# blinkm_mk2b3.net
KiCad netlist of a schematic drawn in EAGLE
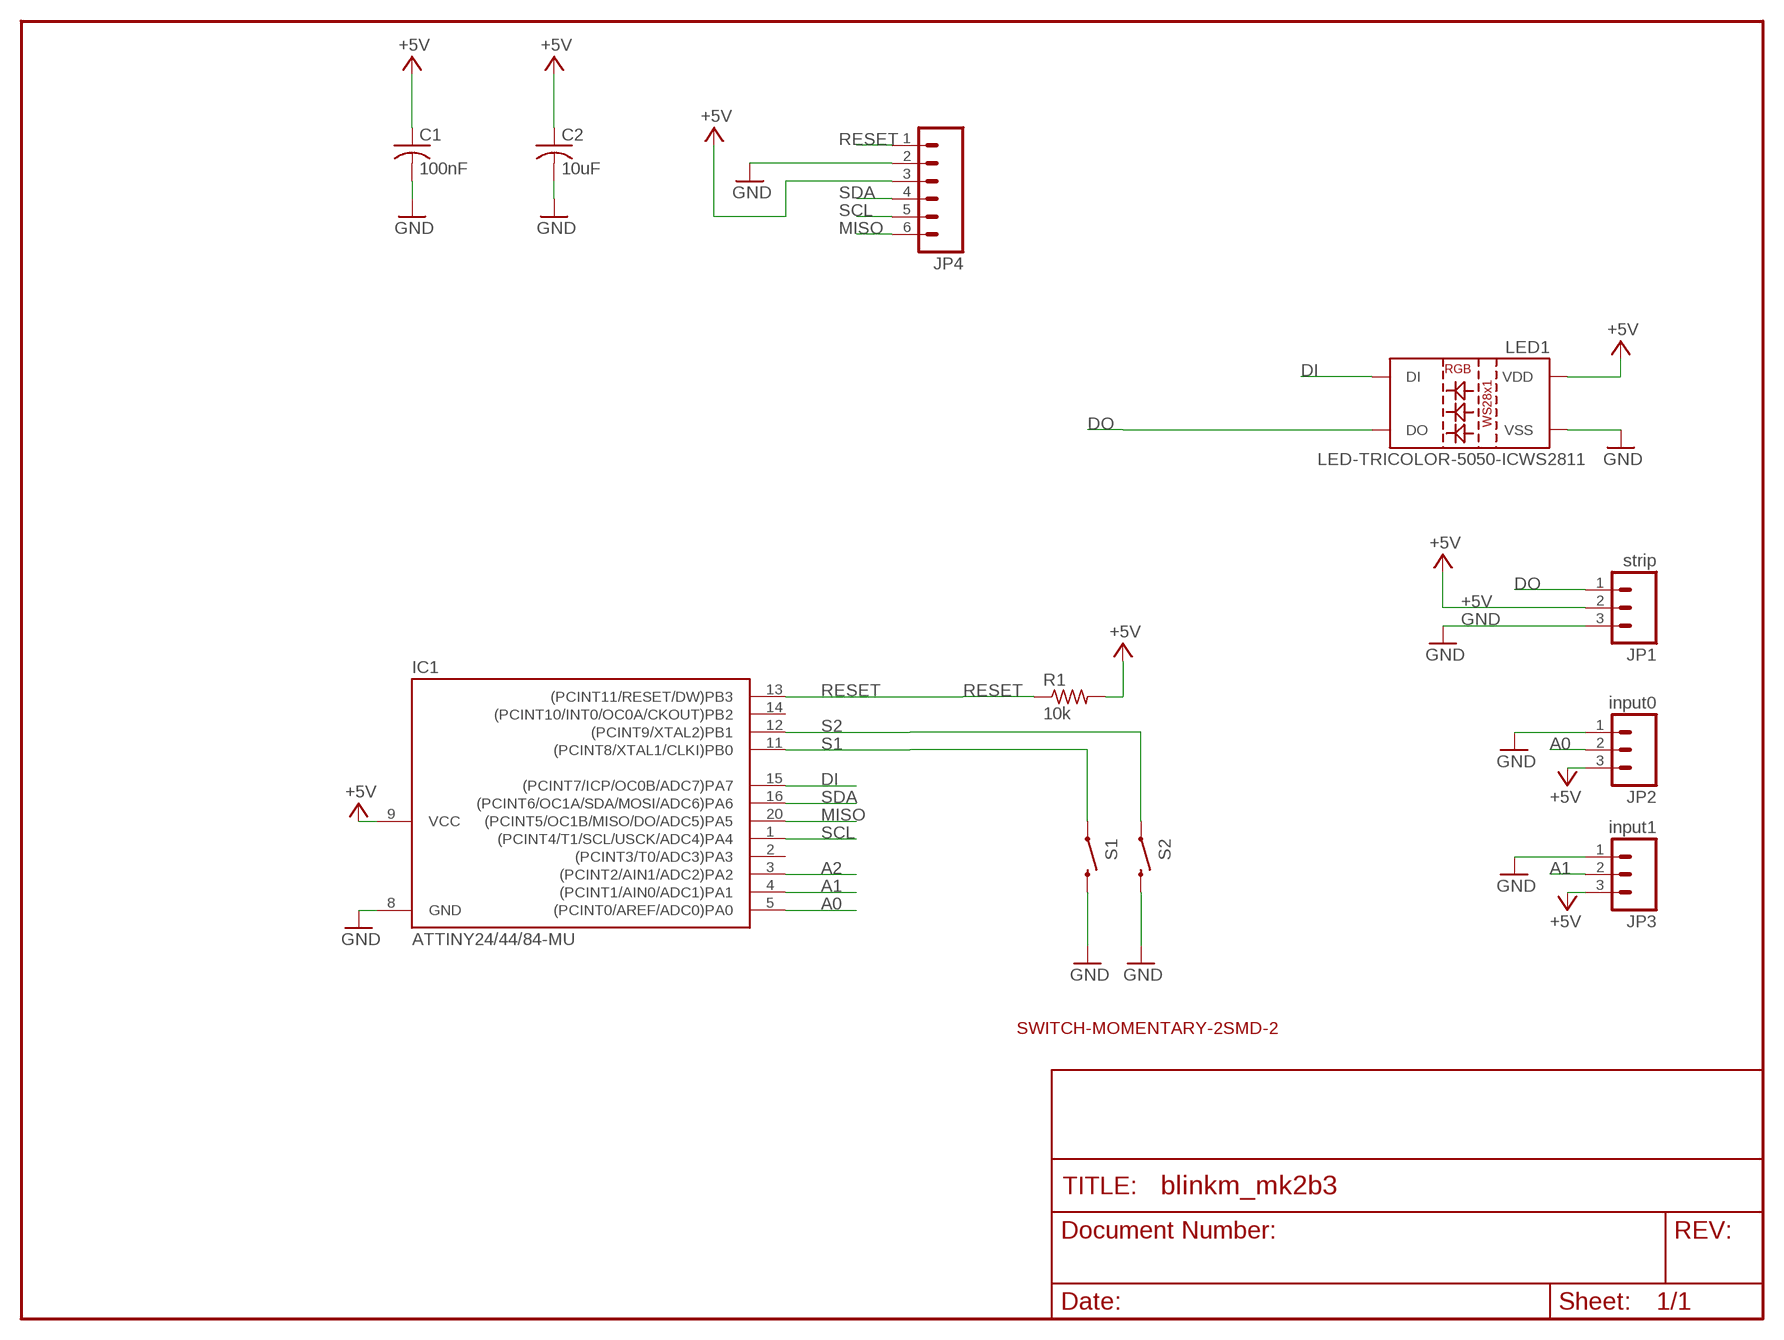
[diagram p0: schematic, sheet 1]

(export (version "E")
  (design (tool "Eeschema 10.0.6"))
  (components
    (comp (ref "C1")
      (value "100nF")
      (footprint "eagle-import:C0603")
      (libsource (lib "eagle-import") (part "C-USC0603"))
    )
    (comp (ref "C2")
      (value "10uF")
      (footprint "eagle-import:C0603")
      (libsource (lib "eagle-import") (part "C-USC0603"))
    )
    (comp (ref "IC1")
      (value "ATTINY24/44/84-MU")
      (footprint "eagle-import:QFN_MLF20")
      (libsource (lib "eagle-import") (part "ATTINY24/44/84-MU"))
    )
    (comp (ref "JP1")
      (value "strip")
      (footprint "eagle-import:1X03")
      (libsource (lib "eagle-import") (part "M03PTH"))
    )
    (comp (ref "JP2")
      (value "input0")
      (footprint "eagle-import:1X03")
      (libsource (lib "eagle-import") (part "M03PTH"))
    )
    (comp (ref "JP3")
      (value "input1")
      (footprint "eagle-import:1X03")
      (libsource (lib "eagle-import") (part "M03PTH"))
    )
    (comp (ref "JP4")
      (value "M06SIP")
      (footprint "eagle-import:1X06")
      (libsource (lib "eagle-import") (part "M06SIP"))
    )
    (comp (ref "LED1")
      (value "LED-TRICOLOR-5050-ICWS2811")
      (footprint "eagle-import:LED-TRICOLOR-5050-IC")
      (libsource (lib "eagle-import") (part "LED-TRICOLOR-5050-ICWS2811"))
    )
    (comp (ref "R1")
      (value "10k")
      (footprint "eagle-import:R0603")
      (libsource (lib "eagle-import") (part "R-US_R0603"))
    )
    (comp (ref "S1")
      (value "SWITCH-MOMENTARY-2SMD-2")
      (footprint "eagle-import:TACTILE_SWITCH_SMD-2")
      (libsource (lib "eagle-import") (part "SWITCH-MOMENTARY-2SMD-2"))
    )
    (comp (ref "S2")
      (value "SWITCH-MOMENTARY-2SMD-2")
      (footprint "eagle-import:TACTILE_SWITCH_SMD-2")
      (libsource (lib "eagle-import") (part "SWITCH-MOMENTARY-2SMD-2"))
    )
  )
  (nets
    (net (code "1") (name "+5V") (class "Default")
      (node (ref "C1") (pin "1") (pinfunction "1_1") (pintype "passive"))
      (node (ref "C2") (pin "1") (pinfunction "1_1") (pintype "passive"))
      (node (ref "IC1") (pin "9") (pinfunction "VCC_9") (pintype "power_in"))
      (node (ref "JP1") (pin "2") (pinfunction "2_2") (pintype "passive"))
      (node (ref "JP2") (pin "3") (pinfunction "3_3") (pintype "passive"))
      (node (ref "JP3") (pin "3") (pinfunction "3_3") (pintype "passive"))
      (node (ref "JP4") (pin "3") (pinfunction "3_3") (pintype "passive"))
      (node (ref "LED1") (pin "3") (pinfunction "VDD_3") (pintype "bidirectional"))
      (node (ref "LED1") (pin "5") (pinfunction "VDD_5") (pintype "bidirectional"))
      (node (ref "R1") (pin "2") (pinfunction "2_2") (pintype "passive"))
    )
    (net (code "2") (name "/A0") (class "Default")
      (node (ref "IC1") (pin "5") (pinfunction "(PCINT0/AREF/ADC0)PA0_5") (pintype "bidirectional"))
      (node (ref "JP2") (pin "2") (pinfunction "2_2") (pintype "passive"))
    )
    (net (code "3") (name "/A1") (class "Default")
      (node (ref "IC1") (pin "4") (pinfunction "(PCINT1/AIN0/ADC1)PA1_4") (pintype "bidirectional"))
      (node (ref "JP3") (pin "2") (pinfunction "2_2") (pintype "passive"))
    )
    (net (code "4") (name "/A2") (class "Default")
      (node (ref "IC1") (pin "3") (pinfunction "(PCINT2/AIN1/ADC2)PA2_3") (pintype "bidirectional"))
    )
    (net (code "5") (name "/DI") (class "Default")
      (node (ref "IC1") (pin "15") (pinfunction "(PCINT7/ICP/OC0B/ADC7)PA7_15") (pintype "bidirectional"))
      (node (ref "LED1") (pin "2") (pinfunction "DI_2") (pintype "bidirectional"))
    )
    (net (code "6") (name "/DO") (class "Default")
      (node (ref "JP1") (pin "1") (pinfunction "1_1") (pintype "passive"))
      (node (ref "LED1") (pin "1") (pinfunction "DO_1") (pintype "bidirectional"))
    )
    (net (code "7") (name "/MISO") (class "Default")
      (node (ref "IC1") (pin "20") (pinfunction "(PCINT5/OC1B/MISO/DO/ADC5)PA5_20") (pintype "bidirectional"))
      (node (ref "JP4") (pin "6") (pinfunction "6_6") (pintype "passive"))
    )
    (net (code "8") (name "/RESET") (class "Default")
      (node (ref "IC1") (pin "13") (pinfunction "(PCINT11/RESET/DW)PB3_13") (pintype "bidirectional"))
      (node (ref "JP4") (pin "1") (pinfunction "1_1") (pintype "passive"))
      (node (ref "R1") (pin "1") (pinfunction "1_1") (pintype "passive"))
    )
    (net (code "9") (name "/S1") (class "Default")
      (node (ref "IC1") (pin "11") (pinfunction "(PCINT8/XTAL1/CLKI)PB0_11") (pintype "bidirectional"))
      (node (ref "S1") (pin "2") (pinfunction "1_2") (pintype "passive"))
    )
    (net (code "10") (name "/S2") (class "Default")
      (node (ref "IC1") (pin "12") (pinfunction "(PCINT9/XTAL2)PB1_12") (pintype "bidirectional"))
      (node (ref "S2") (pin "2") (pinfunction "1_2") (pintype "passive"))
    )
    (net (code "11") (name "/SCL") (class "Default")
      (node (ref "IC1") (pin "1") (pinfunction "(PCINT4/T1/SCL/USCK/ADC4)PA4_1") (pintype "bidirectional"))
      (node (ref "JP4") (pin "5") (pinfunction "5_5") (pintype "passive"))
    )
    (net (code "12") (name "/SDA") (class "Default")
      (node (ref "IC1") (pin "16") (pinfunction "(PCINT6/OC1A/SDA/MOSI/ADC6)PA6_16") (pintype "bidirectional"))
      (node (ref "JP4") (pin "4") (pinfunction "4_4") (pintype "passive"))
    )
    (net (code "13") (name "GND") (class "Default")
      (node (ref "C1") (pin "2") (pinfunction "2_2") (pintype "passive"))
      (node (ref "C2") (pin "2") (pinfunction "2_2") (pintype "passive"))
      (node (ref "IC1") (pin "8") (pinfunction "GND_8") (pintype "power_in"))
      (node (ref "JP1") (pin "3") (pinfunction "3_3") (pintype "passive"))
      (node (ref "JP2") (pin "1") (pinfunction "1_1") (pintype "passive"))
      (node (ref "JP3") (pin "1") (pinfunction "1_1") (pintype "passive"))
      (node (ref "JP4") (pin "2") (pinfunction "2_2") (pintype "passive"))
      (node (ref "LED1") (pin "6") (pinfunction "VSS_6") (pintype "bidirectional"))
      (node (ref "S1") (pin "1") (pinfunction "2_1") (pintype "passive"))
      (node (ref "S2") (pin "1") (pinfunction "2_1") (pintype "passive"))
    )
    (net (code "14") (name "unconnected-(IC1-(PCINT3{slash}T0{slash}ADC3)PA3-Pad2)") (class "Default")
      (node (ref "IC1") (pin "2") (pinfunction "(PCINT3/T0/ADC3)PA3_2") (pintype "bidirectional"))
    )
    (net (code "15") (name "unconnected-(IC1-(PCINT10{slash}INT0{slash}OC0A{slash}CKOUT)PB2-Pad14)") (class "Default")
      (node (ref "IC1") (pin "14") (pinfunction "(PCINT10/INT0/OC0A/CKOUT)PB2_14") (pintype "bidirectional"))
    )
  )
)
